# auto_leg_part.net
KiCad netlist of a schematic drawn in EAGLE
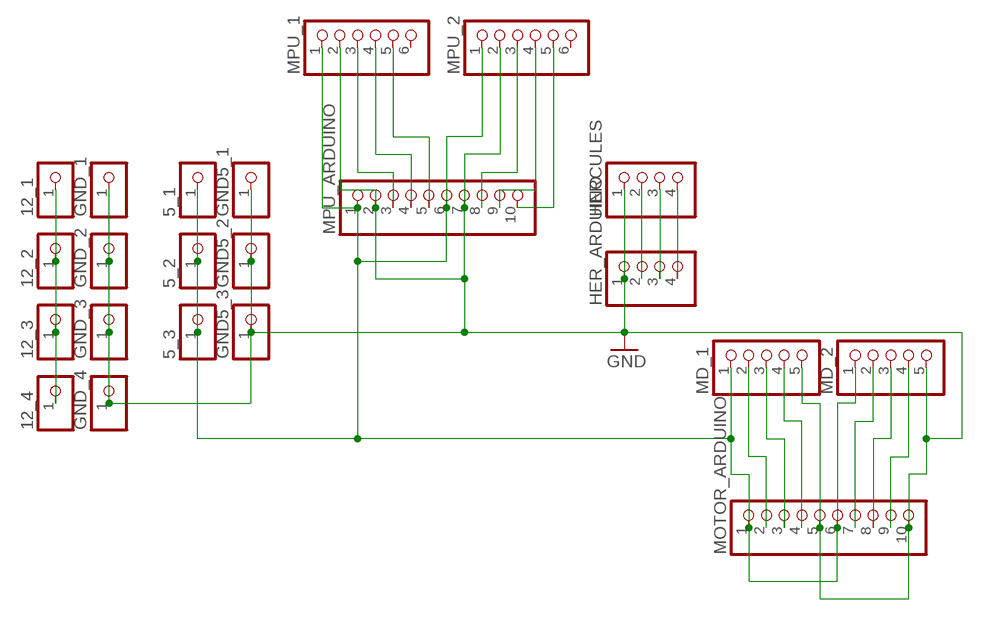
[diagram p0: schematic, sheet 1]

(export (version "E")
  (design (tool "Eeschema 10.0.6"))
  (components
    (comp (ref "5_1")
      (value "PINHD-1X1")
      (footprint "eagle-import:1X01")
      (libsource (lib "eagle-import") (part "PINHD-1X1"))
    )
    (comp (ref "5_2")
      (value "PINHD-1X1")
      (footprint "eagle-import:1X01")
      (libsource (lib "eagle-import") (part "PINHD-1X1"))
    )
    (comp (ref "5_3")
      (value "PINHD-1X1")
      (footprint "eagle-import:1X01")
      (libsource (lib "eagle-import") (part "PINHD-1X1"))
    )
    (comp (ref "12_1")
      (value "PINHD-1X1")
      (footprint "eagle-import:1X01")
      (libsource (lib "eagle-import") (part "PINHD-1X1"))
    )
    (comp (ref "12_2")
      (value "PINHD-1X1")
      (footprint "eagle-import:1X01")
      (libsource (lib "eagle-import") (part "PINHD-1X1"))
    )
    (comp (ref "12_3")
      (value "PINHD-1X1")
      (footprint "eagle-import:1X01")
      (libsource (lib "eagle-import") (part "PINHD-1X1"))
    )
    (comp (ref "12_4")
      (value "PINHD-1X1")
      (footprint "eagle-import:1X01")
      (libsource (lib "eagle-import") (part "PINHD-1X1"))
    )
    (comp (ref "GND5_1")
      (value "PINHD-1X1")
      (footprint "eagle-import:1X01")
      (libsource (lib "eagle-import") (part "PINHD-1X1"))
    )
    (comp (ref "GND5_2")
      (value "PINHD-1X1")
      (footprint "eagle-import:1X01")
      (libsource (lib "eagle-import") (part "PINHD-1X1"))
    )
    (comp (ref "GND5_3")
      (value "PINHD-1X1")
      (footprint "eagle-import:1X01")
      (libsource (lib "eagle-import") (part "PINHD-1X1"))
    )
    (comp (ref "GND_1")
      (value "PINHD-1X1")
      (footprint "eagle-import:1X01")
      (libsource (lib "eagle-import") (part "PINHD-1X1"))
    )
    (comp (ref "GND_2")
      (value "PINHD-1X1")
      (footprint "eagle-import:1X01")
      (libsource (lib "eagle-import") (part "PINHD-1X1"))
    )
    (comp (ref "GND_3")
      (value "PINHD-1X1")
      (footprint "eagle-import:1X01")
      (libsource (lib "eagle-import") (part "PINHD-1X1"))
    )
    (comp (ref "GND_4")
      (value "PINHD-1X1")
      (footprint "eagle-import:1X01")
      (libsource (lib "eagle-import") (part "PINHD-1X1"))
    )
    (comp (ref "HERCULES")
      (value "PINHD-1X4")
      (footprint "eagle-import:1X04")
      (libsource (lib "eagle-import") (part "PINHD-1X4"))
    )
    (comp (ref "HER_ARDUINO")
      (value "PINHD-1X4")
      (footprint "eagle-import:1X04")
      (libsource (lib "eagle-import") (part "PINHD-1X4"))
    )
    (comp (ref "MD_1")
      (value "PINHD-1X5")
      (footprint "eagle-import:1X05")
      (libsource (lib "eagle-import") (part "PINHD-1X5"))
    )
    (comp (ref "MD_2")
      (value "PINHD-1X5")
      (footprint "eagle-import:1X05")
      (libsource (lib "eagle-import") (part "PINHD-1X5"))
    )
    (comp (ref "MOTOR_ARDUINO")
      (value "PINHD-1X10")
      (footprint "eagle-import:1X10")
      (libsource (lib "eagle-import") (part "PINHD-1X10"))
    )
    (comp (ref "MPU_1")
      (value "PINHD-1X6")
      (footprint "eagle-import:1X06")
      (libsource (lib "eagle-import") (part "PINHD-1X6"))
    )
    (comp (ref "MPU_2")
      (value "PINHD-1X6")
      (footprint "eagle-import:1X06")
      (libsource (lib "eagle-import") (part "PINHD-1X6"))
    )
    (comp (ref "MPU_ARDUINO")
      (value "PINHD-1X10")
      (footprint "eagle-import:1X10")
      (libsource (lib "eagle-import") (part "PINHD-1X10"))
    )
  )
  (nets
    (net (code "1") (name "GND") (class "Default")
      (node (ref "GND5_1") (pin "1") (pinfunction "1_1") (pintype "passive"))
      (node (ref "GND5_2") (pin "1") (pinfunction "1_1") (pintype "passive"))
      (node (ref "GND5_3") (pin "1") (pinfunction "1_1") (pintype "passive"))
      (node (ref "GND_1") (pin "1") (pinfunction "1_1") (pintype "passive"))
      (node (ref "GND_2") (pin "1") (pinfunction "1_1") (pintype "passive"))
      (node (ref "GND_3") (pin "1") (pinfunction "1_1") (pintype "passive"))
      (node (ref "GND_4") (pin "1") (pinfunction "1_1") (pintype "passive"))
      (node (ref "HERCULES") (pin "1") (pinfunction "1_1") (pintype "passive"))
      (node (ref "HER_ARDUINO") (pin "1") (pinfunction "1_1") (pintype "passive"))
      (node (ref "MD_1") (pin "5") (pinfunction "5_5") (pintype "passive"))
      (node (ref "MD_2") (pin "5") (pinfunction "5_5") (pintype "passive"))
      (node (ref "MOTOR_ARDUINO") (pin "10") (pinfunction "10_10") (pintype "passive"))
      (node (ref "MOTOR_ARDUINO") (pin "5") (pinfunction "5_5") (pintype "passive"))
      (node (ref "MPU_1") (pin "2") (pinfunction "2_2") (pintype "passive"))
      (node (ref "MPU_2") (pin "2") (pinfunction "2_2") (pintype "passive"))
      (node (ref "MPU_ARDUINO") (pin "2") (pinfunction "2_2") (pintype "passive"))
      (node (ref "MPU_ARDUINO") (pin "7") (pinfunction "7_7") (pintype "passive"))
    )
    (net (code "2") (name "Net-(5_1-Pad1)") (class "Default")
      (node (ref "5_1") (pin "1") (pinfunction "1_1") (pintype "passive"))
      (node (ref "5_2") (pin "1") (pinfunction "1_1") (pintype "passive"))
      (node (ref "5_3") (pin "1") (pinfunction "1_1") (pintype "passive"))
      (node (ref "MD_1") (pin "1") (pinfunction "1_1") (pintype "passive"))
      (node (ref "MD_2") (pin "1") (pinfunction "1_1") (pintype "passive"))
      (node (ref "MOTOR_ARDUINO") (pin "1") (pinfunction "1_1") (pintype "passive"))
      (node (ref "MOTOR_ARDUINO") (pin "6") (pinfunction "6_6") (pintype "passive"))
      (node (ref "MPU_1") (pin "1") (pinfunction "1_1") (pintype "passive"))
      (node (ref "MPU_2") (pin "1") (pinfunction "1_1") (pintype "passive"))
      (node (ref "MPU_ARDUINO") (pin "1") (pinfunction "1_1") (pintype "passive"))
      (node (ref "MPU_ARDUINO") (pin "6") (pinfunction "6_6") (pintype "passive"))
    )
    (net (code "3") (name "Net-(12_1-Pad1)") (class "Default")
      (node (ref "12_1") (pin "1") (pinfunction "1_1") (pintype "passive"))
      (node (ref "12_2") (pin "1") (pinfunction "1_1") (pintype "passive"))
      (node (ref "12_3") (pin "1") (pinfunction "1_1") (pintype "passive"))
      (node (ref "12_4") (pin "1") (pinfunction "1_1") (pintype "passive"))
    )
    (net (code "4") (name "Net-(HERCULES-Pad2)") (class "Default")
      (node (ref "HERCULES") (pin "2") (pinfunction "2_2") (pintype "passive"))
      (node (ref "HER_ARDUINO") (pin "2") (pinfunction "2_2") (pintype "passive"))
    )
    (net (code "5") (name "Net-(HERCULES-Pad3)") (class "Default")
      (node (ref "HERCULES") (pin "3") (pinfunction "3_3") (pintype "passive"))
      (node (ref "HER_ARDUINO") (pin "3") (pinfunction "3_3") (pintype "passive"))
    )
    (net (code "6") (name "Net-(HERCULES-Pad4)") (class "Default")
      (node (ref "HERCULES") (pin "4") (pinfunction "4_4") (pintype "passive"))
      (node (ref "HER_ARDUINO") (pin "4") (pinfunction "4_4") (pintype "passive"))
    )
    (net (code "7") (name "Net-(MD_1-Pad2)") (class "Default")
      (node (ref "MD_1") (pin "2") (pinfunction "2_2") (pintype "passive"))
      (node (ref "MOTOR_ARDUINO") (pin "2") (pinfunction "2_2") (pintype "passive"))
    )
    (net (code "8") (name "Net-(MD_1-Pad3)") (class "Default")
      (node (ref "MD_1") (pin "3") (pinfunction "3_3") (pintype "passive"))
      (node (ref "MOTOR_ARDUINO") (pin "3") (pinfunction "3_3") (pintype "passive"))
    )
    (net (code "9") (name "Net-(MD_1-Pad4)") (class "Default")
      (node (ref "MD_1") (pin "4") (pinfunction "4_4") (pintype "passive"))
      (node (ref "MOTOR_ARDUINO") (pin "4") (pinfunction "4_4") (pintype "passive"))
    )
    (net (code "10") (name "Net-(MD_2-Pad2)") (class "Default")
      (node (ref "MD_2") (pin "2") (pinfunction "2_2") (pintype "passive"))
      (node (ref "MOTOR_ARDUINO") (pin "7") (pinfunction "7_7") (pintype "passive"))
    )
    (net (code "11") (name "Net-(MD_2-Pad3)") (class "Default")
      (node (ref "MD_2") (pin "3") (pinfunction "3_3") (pintype "passive"))
      (node (ref "MOTOR_ARDUINO") (pin "8") (pinfunction "8_8") (pintype "passive"))
    )
    (net (code "12") (name "Net-(MD_2-Pad4)") (class "Default")
      (node (ref "MD_2") (pin "4") (pinfunction "4_4") (pintype "passive"))
      (node (ref "MOTOR_ARDUINO") (pin "9") (pinfunction "9_9") (pintype "passive"))
    )
    (net (code "13") (name "Net-(MPU_1-Pad3)") (class "Default")
      (node (ref "MPU_1") (pin "3") (pinfunction "3_3") (pintype "passive"))
      (node (ref "MPU_ARDUINO") (pin "3") (pinfunction "3_3") (pintype "passive"))
    )
    (net (code "14") (name "Net-(MPU_1-Pad4)") (class "Default")
      (node (ref "MPU_1") (pin "4") (pinfunction "4_4") (pintype "passive"))
      (node (ref "MPU_ARDUINO") (pin "4") (pinfunction "4_4") (pintype "passive"))
    )
    (net (code "15") (name "Net-(MPU_1-Pad5)") (class "Default")
      (node (ref "MPU_1") (pin "5") (pinfunction "5_5") (pintype "passive"))
      (node (ref "MPU_ARDUINO") (pin "5") (pinfunction "5_5") (pintype "passive"))
    )
    (net (code "16") (name "Net-(MPU_2-Pad3)") (class "Default")
      (node (ref "MPU_2") (pin "3") (pinfunction "3_3") (pintype "passive"))
      (node (ref "MPU_ARDUINO") (pin "8") (pinfunction "8_8") (pintype "passive"))
    )
    (net (code "17") (name "Net-(MPU_2-Pad4)") (class "Default")
      (node (ref "MPU_2") (pin "4") (pinfunction "4_4") (pintype "passive"))
      (node (ref "MPU_ARDUINO") (pin "9") (pinfunction "9_9") (pintype "passive"))
    )
    (net (code "18") (name "Net-(MPU_2-Pad5)") (class "Default")
      (node (ref "MPU_2") (pin "5") (pinfunction "5_5") (pintype "passive"))
      (node (ref "MPU_ARDUINO") (pin "10") (pinfunction "10_10") (pintype "passive"))
    )
    (net (code "19") (name "unconnected-(MPU_1-Pad6)") (class "Default")
      (node (ref "MPU_1") (pin "6") (pinfunction "6_6") (pintype "passive"))
    )
    (net (code "20") (name "unconnected-(MPU_2-Pad6)") (class "Default")
      (node (ref "MPU_2") (pin "6") (pinfunction "6_6") (pintype "passive"))
    )
  )
)
